# Public_CPU_Sub_Power_Supplies.net
KiCad netlist of a schematic drawn in Altium Designer
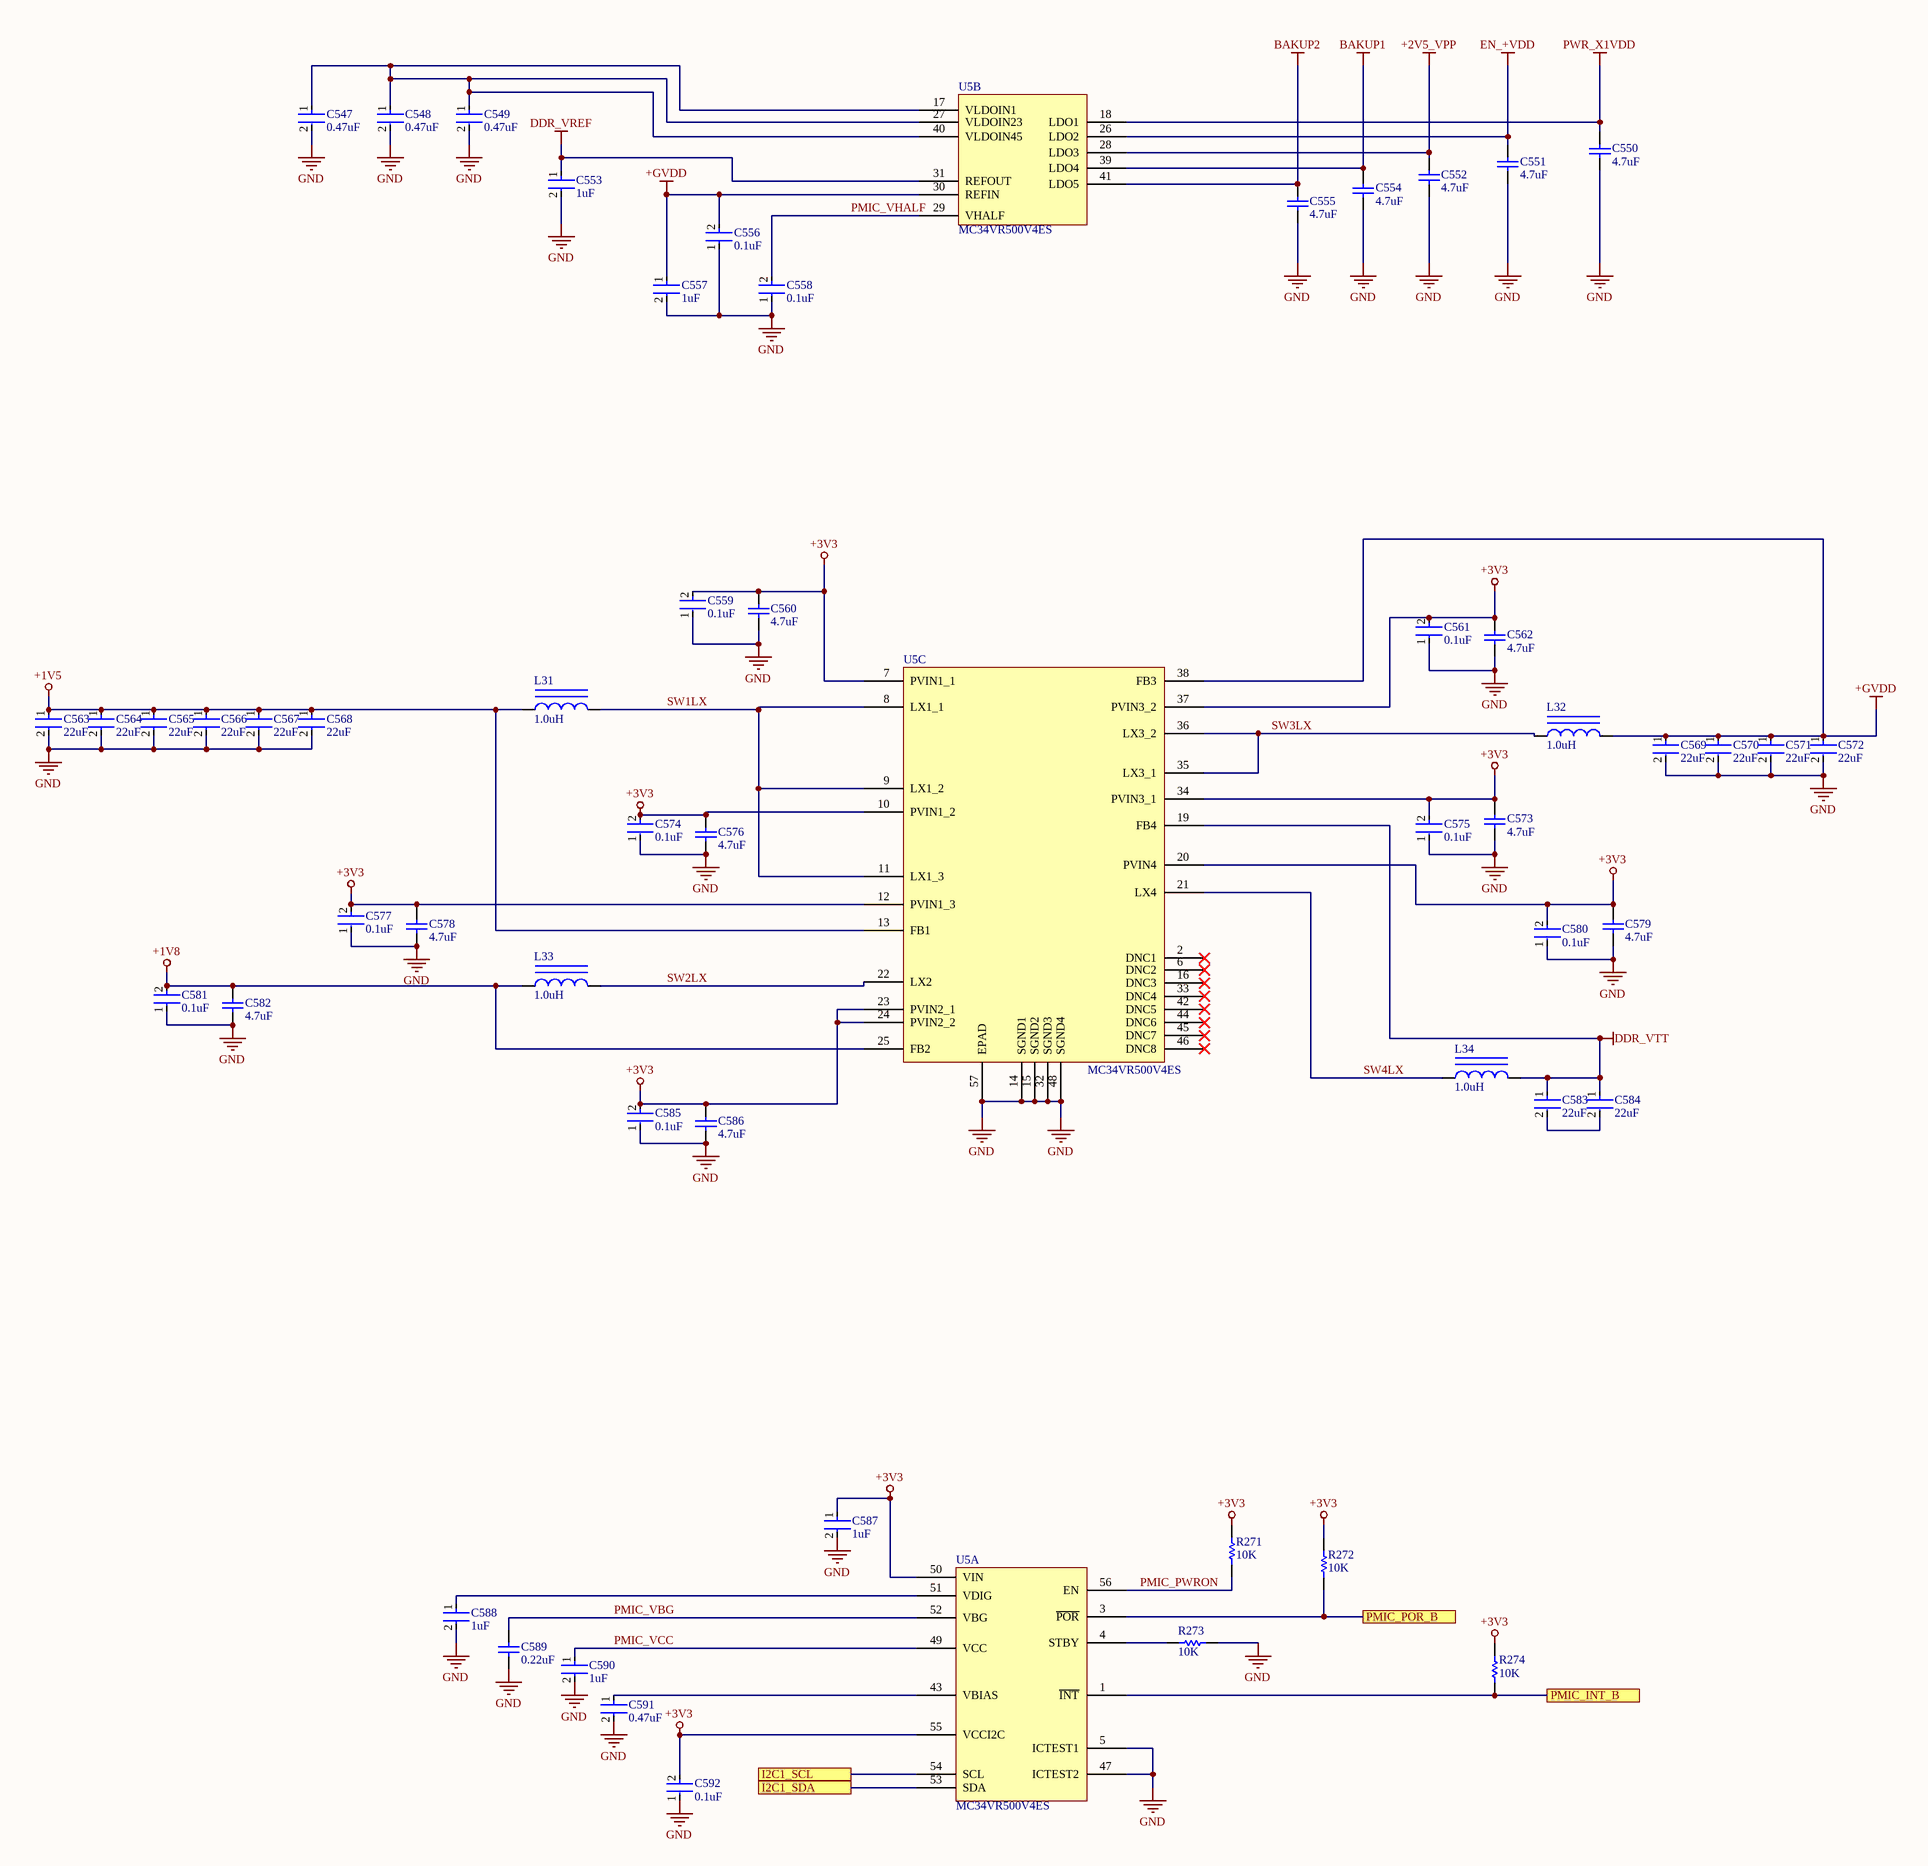
[diagram p0: Public_CPU_Sub_Power_Supplies.SchDoc]

(export (version "E")
  (design (tool "Eeschema 10.0.6"))
  (components
    (comp (ref "C547")
      (value "0.47uF")
      (footprint "FP-GRM188-0_1-e0_2_0_5-IPC_B")
      (description "Chip Multilayer Ceramic Capacitors for General Purpose, 0603, 0.47uF, X7R, 15%, 10%, 16V")
      (fields (field (name "VOLTAGE") "16V") (field (name "TOLERANCE") "10%"))
      (libsource (lib "Altium Content Vault") (part "11868f565c42a9108669ba33697ecf6"))
    )
    (comp (ref "C548")
      (value "0.47uF")
      (footprint "FP-GRM188-0_1-e0_2_0_5-IPC_B")
      (description "Chip Multilayer Ceramic Capacitors for General Purpose, 0603, 0.47uF, X7R, 15%, 10%, 16V")
      (fields (field (name "VOLTAGE") "16V") (field (name "TOLERANCE") "10%"))
      (libsource (lib "Altium Content Vault") (part "11868f565c42a9108669ba33697ecf6"))
    )
    (comp (ref "C549")
      (value "0.47uF")
      (footprint "FP-GRM188-0_1-e0_2_0_5-IPC_B")
      (description "Chip Multilayer Ceramic Capacitors for General Purpose, 0603, 0.47uF, X7R, 15%, 10%, 16V")
      (fields (field (name "VOLTAGE") "16V") (field (name "TOLERANCE") "10%"))
      (libsource (lib "Altium Content Vault") (part "11868f565c42a9108669ba33697ecf6"))
    )
    (comp (ref "C550")
      (value "4.7uF")
      (footprint "CAPC2013X145X50ML20T25")
      (fields (field (name "MANUFACTURER") "Kemet") (field (name "PART NUMBER") "C0805C475K3PACTU"))
      (libsource (lib "Altium Content Vault") (part "CAP"))
    )
    (comp (ref "C551")
      (value "4.7uF")
      (footprint "CAPC2013X145X50ML20T25")
      (fields (field (name "MANUFACTURER") "Kemet") (field (name "PART NUMBER") "C0805C475K3PACTU"))
      (libsource (lib "Altium Content Vault") (part "CAP"))
    )
    (comp (ref "C552")
      (value "4.7uF")
      (footprint "CAPC2013X145X50ML20T25")
      (fields (field (name "MANUFACTURER") "Kemet") (field (name "PART NUMBER") "C0805C475K3PACTU"))
      (libsource (lib "Altium Content Vault") (part "CAP"))
    )
    (comp (ref "C553")
      (value "1uF")
      (footprint "FP-GRM15-0_1-MFG")
      (description "CAP CER 1UF 10V X5R 0402")
      (fields
        (field (name "OCTOPART") "https://octopart.com/grm155r61a105ke15d-murata-197442")
        (field (name "MANUFACTURER PART NUMBER") "GRM155R61A105KE15D")
      )
      (libsource (lib "Altium Content Vault") (part "02cd4be3c70576c341d710602a673aa"))
    )
    (comp (ref "C554")
      (value "4.7uF")
      (footprint "CAPC2013X145X50ML20T25")
      (fields (field (name "MANUFACTURER") "Kemet") (field (name "PART NUMBER") "C0805C475K3PACTU"))
      (libsource (lib "Altium Content Vault") (part "CAP"))
    )
    (comp (ref "C555")
      (value "4.7uF")
      (footprint "CAPC2013X145X50ML20T25")
      (fields (field (name "MANUFACTURER") "Kemet") (field (name "PART NUMBER") "C0805C475K3PACTU"))
      (libsource (lib "Altium Content Vault") (part "CAP"))
    )
    (comp (ref "C556")
      (value "0.1uF")
      (footprint "FP-GRM15-MFG")
      (description "CAP CER 0.1UF 16V X7R 0402")
      (fields (field (name "MANUFACTURER PART NUMBER") "GRM155R71C104KA88D") (field (name "TOLERANCE") "10%"))
      (libsource (lib "Altium Content Vault") (part "236180d848d6139a670b325ea6854c9"))
    )
    (comp (ref "C557")
      (value "1uF")
      (footprint "FP-GRM15-0_1-MFG")
      (description "CAP CER 1UF 10V X5R 0402")
      (fields
        (field (name "OCTOPART") "https://octopart.com/grm155r61a105ke15d-murata-197442")
        (field (name "MANUFACTURER PART NUMBER") "GRM155R61A105KE15D")
      )
      (libsource (lib "Altium Content Vault") (part "02cd4be3c70576c341d710602a673aa"))
    )
    (comp (ref "C558")
      (value "0.1uF")
      (footprint "FP-GRM15-MFG")
      (description "CAP CER 0.1UF 16V X7R 0402")
      (fields (field (name "MANUFACTURER PART NUMBER") "GRM155R71C104KA88D") (field (name "TOLERANCE") "10%"))
      (libsource (lib "Altium Content Vault") (part "236180d848d6139a670b325ea6854c9"))
    )
    (comp (ref "C559")
      (value "0.1uF")
      (footprint "FP-GRM15-MFG")
      (description "CAP CER 0.1UF 16V X7R 0402")
      (fields (field (name "MANUFACTURER PART NUMBER") "GRM155R71C104KA88D") (field (name "TOLERANCE") "10%"))
      (libsource (lib "Altium Content Vault") (part "236180d848d6139a670b325ea6854c9"))
    )
    (comp (ref "C560")
      (value "4.7uF")
      (footprint "CAPC2013X145X50ML20T25")
      (fields (field (name "MANUFACTURER") "Kemet") (field (name "PART NUMBER") "C0805C475K3PACTU"))
      (libsource (lib "Altium Content Vault") (part "CAP"))
    )
    (comp (ref "C561")
      (value "0.1uF")
      (footprint "FP-GRM15-MFG")
      (description "CAP CER 0.1UF 16V X7R 0402")
      (fields (field (name "MANUFACTURER PART NUMBER") "GRM155R71C104KA88D") (field (name "TOLERANCE") "10%"))
      (libsource (lib "Altium Content Vault") (part "236180d848d6139a670b325ea6854c9"))
    )
    (comp (ref "C562")
      (value "4.7uF")
      (footprint "CAPC2013X145X50ML20T25")
      (fields (field (name "MANUFACTURER") "Kemet") (field (name "PART NUMBER") "C0805C475K3PACTU"))
      (libsource (lib "Altium Content Vault") (part "CAP"))
    )
    (comp (ref "C563")
      (value "22uF")
      (footprint "FP-GRM21B-0_15-MFG")
      (description "Chip Multilayer Ceramic Capacitors for General Purpose, 0805, 22uF, X5R, 15%, 20%, 6.3V")
      (fields (field (name "VOLTAGE") "6.3V") (field (name "TOLERANCE") "20%"))
      (libsource (lib "Altium Content Vault") (part "b4654b650e69147ec39a6b967a45e02"))
    )
    (comp (ref "C564")
      (value "22uF")
      (footprint "FP-GRM21B-0_15-MFG")
      (description "Chip Multilayer Ceramic Capacitors for General Purpose, 0805, 22uF, X5R, 15%, 20%, 6.3V")
      (fields (field (name "VOLTAGE") "6.3V") (field (name "TOLERANCE") "20%"))
      (libsource (lib "Altium Content Vault") (part "b4654b650e69147ec39a6b967a45e02"))
    )
    (comp (ref "C565")
      (value "22uF")
      (footprint "FP-GRM21B-0_15-MFG")
      (description "Chip Multilayer Ceramic Capacitors for General Purpose, 0805, 22uF, X5R, 15%, 20%, 6.3V")
      (fields (field (name "VOLTAGE") "6.3V") (field (name "TOLERANCE") "20%"))
      (libsource (lib "Altium Content Vault") (part "b4654b650e69147ec39a6b967a45e02"))
    )
    (comp (ref "C566")
      (value "22uF")
      (footprint "FP-GRM21B-0_15-MFG")
      (description "Chip Multilayer Ceramic Capacitors for General Purpose, 0805, 22uF, X5R, 15%, 20%, 6.3V")
      (fields (field (name "VOLTAGE") "6.3V") (field (name "TOLERANCE") "20%"))
      (libsource (lib "Altium Content Vault") (part "b4654b650e69147ec39a6b967a45e02"))
    )
    (comp (ref "C567")
      (value "22uF")
      (footprint "FP-GRM21B-0_15-MFG")
      (description "Chip Multilayer Ceramic Capacitors for General Purpose, 0805, 22uF, X5R, 15%, 20%, 6.3V")
      (fields (field (name "VOLTAGE") "6.3V") (field (name "TOLERANCE") "20%"))
      (libsource (lib "Altium Content Vault") (part "b4654b650e69147ec39a6b967a45e02"))
    )
    (comp (ref "C568")
      (value "22uF")
      (footprint "FP-GRM21B-0_15-MFG")
      (description "Chip Multilayer Ceramic Capacitors for General Purpose, 0805, 22uF, X5R, 15%, 20%, 6.3V")
      (fields (field (name "VOLTAGE") "6.3V") (field (name "TOLERANCE") "20%"))
      (libsource (lib "Altium Content Vault") (part "b4654b650e69147ec39a6b967a45e02"))
    )
    (comp (ref "C569")
      (value "22uF")
      (footprint "FP-GRM21B-0_15-MFG")
      (description "Chip Multilayer Ceramic Capacitors for General Purpose, 0805, 22uF, X5R, 15%, 20%, 6.3V")
      (fields (field (name "VOLTAGE") "6.3V") (field (name "TOLERANCE") "20%"))
      (libsource (lib "Altium Content Vault") (part "b4654b650e69147ec39a6b967a45e02"))
    )
    (comp (ref "C570")
      (value "22uF")
      (footprint "FP-GRM21B-0_15-MFG")
      (description "Chip Multilayer Ceramic Capacitors for General Purpose, 0805, 22uF, X5R, 15%, 20%, 6.3V")
      (fields (field (name "VOLTAGE") "6.3V") (field (name "TOLERANCE") "20%"))
      (libsource (lib "Altium Content Vault") (part "b4654b650e69147ec39a6b967a45e02"))
    )
    (comp (ref "C571")
      (value "22uF")
      (footprint "FP-GRM21B-0_15-MFG")
      (description "Chip Multilayer Ceramic Capacitors for General Purpose, 0805, 22uF, X5R, 15%, 20%, 6.3V")
      (fields (field (name "VOLTAGE") "6.3V") (field (name "TOLERANCE") "20%"))
      (libsource (lib "Altium Content Vault") (part "b4654b650e69147ec39a6b967a45e02"))
    )
    (comp (ref "C572")
      (value "22uF")
      (footprint "FP-GRM21B-0_15-MFG")
      (description "Chip Multilayer Ceramic Capacitors for General Purpose, 0805, 22uF, X5R, 15%, 20%, 6.3V")
      (fields (field (name "VOLTAGE") "6.3V") (field (name "TOLERANCE") "20%"))
      (libsource (lib "Altium Content Vault") (part "b4654b650e69147ec39a6b967a45e02"))
    )
    (comp (ref "C573")
      (value "4.7uF")
      (footprint "CAPC2013X145X50ML20T25")
      (fields (field (name "MANUFACTURER") "Kemet") (field (name "PART NUMBER") "C0805C475K3PACTU"))
      (libsource (lib "Altium Content Vault") (part "CAP"))
    )
    (comp (ref "C574")
      (value "0.1uF")
      (footprint "FP-GRM15-MFG")
      (description "CAP CER 0.1UF 16V X7R 0402")
      (fields (field (name "MANUFACTURER PART NUMBER") "GRM155R71C104KA88D") (field (name "TOLERANCE") "10%"))
      (libsource (lib "Altium Content Vault") (part "236180d848d6139a670b325ea6854c9"))
    )
    (comp (ref "C575")
      (value "0.1uF")
      (footprint "FP-GRM15-MFG")
      (description "CAP CER 0.1UF 16V X7R 0402")
      (fields (field (name "MANUFACTURER PART NUMBER") "GRM155R71C104KA88D") (field (name "TOLERANCE") "10%"))
      (libsource (lib "Altium Content Vault") (part "236180d848d6139a670b325ea6854c9"))
    )
    (comp (ref "C576")
      (value "4.7uF")
      (footprint "CAPC2013X145X50ML20T25")
      (fields (field (name "MANUFACTURER") "Kemet") (field (name "PART NUMBER") "C0805C475K3PACTU"))
      (libsource (lib "Altium Content Vault") (part "CAP"))
    )
    (comp (ref "C577")
      (value "0.1uF")
      (footprint "FP-GRM15-MFG")
      (description "CAP CER 0.1UF 16V X7R 0402")
      (fields (field (name "MANUFACTURER PART NUMBER") "GRM155R71C104KA88D") (field (name "TOLERANCE") "10%"))
      (libsource (lib "Altium Content Vault") (part "236180d848d6139a670b325ea6854c9"))
    )
    (comp (ref "C578")
      (value "4.7uF")
      (footprint "CAPC2013X145X50ML20T25")
      (fields (field (name "MANUFACTURER") "Kemet") (field (name "PART NUMBER") "C0805C475K3PACTU"))
      (libsource (lib "Altium Content Vault") (part "CAP"))
    )
    (comp (ref "C579")
      (value "4.7uF")
      (footprint "CAPC2013X145X50ML20T25")
      (fields (field (name "MANUFACTURER") "Kemet") (field (name "PART NUMBER") "C0805C475K3PACTU"))
      (libsource (lib "Altium Content Vault") (part "CAP"))
    )
    (comp (ref "C580")
      (value "0.1uF")
      (footprint "FP-GRM15-MFG")
      (description "CAP CER 0.1UF 16V X7R 0402")
      (fields (field (name "MANUFACTURER PART NUMBER") "GRM155R71C104KA88D") (field (name "TOLERANCE") "10%"))
      (libsource (lib "Altium Content Vault") (part "236180d848d6139a670b325ea6854c9"))
    )
    (comp (ref "C581")
      (value "0.1uF")
      (footprint "FP-GRM15-MFG")
      (description "CAP CER 0.1UF 16V X7R 0402")
      (fields (field (name "MANUFACTURER PART NUMBER") "GRM155R71C104KA88D") (field (name "TOLERANCE") "10%"))
      (libsource (lib "Altium Content Vault") (part "236180d848d6139a670b325ea6854c9"))
    )
    (comp (ref "C582")
      (value "4.7uF")
      (footprint "CAPC2013X145X50ML20T25")
      (fields (field (name "MANUFACTURER") "Kemet") (field (name "PART NUMBER") "C0805C475K3PACTU"))
      (libsource (lib "Altium Content Vault") (part "CAP"))
    )
    (comp (ref "C583")
      (value "22uF")
      (footprint "FP-GRM21B-0_15-MFG")
      (description "Chip Multilayer Ceramic Capacitors for General Purpose, 0805, 22uF, X5R, 15%, 20%, 6.3V")
      (fields (field (name "VOLTAGE") "6.3V") (field (name "TOLERANCE") "20%"))
      (libsource (lib "Altium Content Vault") (part "b4654b650e69147ec39a6b967a45e02"))
    )
    (comp (ref "C584")
      (value "22uF")
      (footprint "FP-GRM21B-0_15-MFG")
      (description "Chip Multilayer Ceramic Capacitors for General Purpose, 0805, 22uF, X5R, 15%, 20%, 6.3V")
      (fields (field (name "VOLTAGE") "6.3V") (field (name "TOLERANCE") "20%"))
      (libsource (lib "Altium Content Vault") (part "b4654b650e69147ec39a6b967a45e02"))
    )
    (comp (ref "C585")
      (value "0.1uF")
      (footprint "FP-GRM15-MFG")
      (description "CAP CER 0.1UF 16V X7R 0402")
      (fields (field (name "MANUFACTURER PART NUMBER") "GRM155R71C104KA88D") (field (name "TOLERANCE") "10%"))
      (libsource (lib "Altium Content Vault") (part "236180d848d6139a670b325ea6854c9"))
    )
    (comp (ref "C586")
      (value "4.7uF")
      (footprint "CAPC2013X145X50ML20T25")
      (fields (field (name "MANUFACTURER") "Kemet") (field (name "PART NUMBER") "C0805C475K3PACTU"))
      (libsource (lib "Altium Content Vault") (part "CAP"))
    )
    (comp (ref "C587")
      (value "1uF")
      (footprint "FP-GRM15-0_1-MFG")
      (description "CAP CER 1UF 10V X5R 0402")
      (fields
        (field (name "OCTOPART") "https://octopart.com/grm155r61a105ke15d-murata-197442")
        (field (name "MANUFACTURER PART NUMBER") "GRM155R61A105KE15D")
      )
      (libsource (lib "Altium Content Vault") (part "02cd4be3c70576c341d710602a673aa"))
    )
    (comp (ref "C588")
      (value "1uF")
      (footprint "FP-GRM15-0_1-MFG")
      (description "CAP CER 1UF 10V X5R 0402")
      (fields
        (field (name "OCTOPART") "https://octopart.com/grm155r61a105ke15d-murata-197442")
        (field (name "MANUFACTURER PART NUMBER") "GRM155R61A105KE15D")
      )
      (libsource (lib "Altium Content Vault") (part "02cd4be3c70576c341d710602a673aa"))
    )
    (comp (ref "C589")
      (value "0.22uF")
      (footprint "CAPC1005X55X25NL05T10")
      (description "Chip Capacitor, 220 nF, +/- 10%, 10 V, -55 to 85 degC, 0402 (1005 Metric), RoHS, Tape and Reel")
      (fields (field (name "MANUFACTURER") "Basic Passives") (field (name "TOLERANCE") "10%"))
      (libsource (lib "Altium Content Vault") (part "CAP-NP-2"))
    )
    (comp (ref "C590")
      (value "1uF")
      (footprint "FP-GRM15-0_1-MFG")
      (description "CAP CER 1UF 10V X5R 0402")
      (fields
        (field (name "OCTOPART") "https://octopart.com/grm155r61a105ke15d-murata-197442")
        (field (name "MANUFACTURER PART NUMBER") "GRM155R61A105KE15D")
      )
      (libsource (lib "Altium Content Vault") (part "02cd4be3c70576c341d710602a673aa"))
    )
    (comp (ref "C591")
      (value "0.47uF")
      (footprint "FP-GRM188-0_1-e0_2_0_5-IPC_B")
      (description "Chip Multilayer Ceramic Capacitors for General Purpose, 0603, 0.47uF, X7R, 15%, 10%, 16V")
      (fields (field (name "VOLTAGE") "16V") (field (name "TOLERANCE") "10%"))
      (libsource (lib "Altium Content Vault") (part "11868f565c42a9108669ba33697ecf6"))
    )
    (comp (ref "C592")
      (value "0.1uF")
      (footprint "FP-GRM15-MFG")
      (description "CAP CER 0.1UF 16V X7R 0402")
      (fields (field (name "MANUFACTURER PART NUMBER") "GRM155R71C104KA88D") (field (name "TOLERANCE") "10%"))
      (libsource (lib "Altium Content Vault") (part "236180d848d6139a670b325ea6854c9"))
    )
    (comp (ref "L31")
      (value "1.0uH")
      (footprint "BOUR-CM45_L")
      (description "Chip Inductor, 1 uH, +/- 10%, 450 mA, -40 to 125 degC, 2-Pin SMD (1812), RoHS, Tape and Reel")
      (fields (field (name "MANUFACTURER") "Bourns"))
      (libsource (lib "Altium Content Vault") (part "IND-IRON-2"))
    )
    (comp (ref "L32")
      (value "1.0uH")
      (footprint "BOUR-CM45_L")
      (description "Chip Inductor, 1 uH, +/- 10%, 450 mA, -40 to 125 degC, 2-Pin SMD (1812), RoHS, Tape and Reel")
      (fields (field (name "MANUFACTURER") "Bourns"))
      (libsource (lib "Altium Content Vault") (part "IND-IRON-2"))
    )
    (comp (ref "L33")
      (value "1.0uH")
      (footprint "BOUR-CM45_L")
      (description "Chip Inductor, 1 uH, +/- 10%, 450 mA, -40 to 125 degC, 2-Pin SMD (1812), RoHS, Tape and Reel")
      (fields (field (name "MANUFACTURER") "Bourns"))
      (libsource (lib "Altium Content Vault") (part "IND-IRON-2"))
    )
    (comp (ref "L34")
      (value "1.0uH")
      (footprint "BOUR-CM45_L")
      (description "Chip Inductor, 1 uH, +/- 10%, 450 mA, -40 to 125 degC, 2-Pin SMD (1812), RoHS, Tape and Reel")
      (fields (field (name "MANUFACTURER") "Bourns"))
      (libsource (lib "Altium Content Vault") (part "IND-IRON-2"))
    )
    (comp (ref "R271")
      (value "10K")
      (footprint "RESC1005X40X25LL05T05")
      (description "Chip Resistor, 10 KOhm, +/- 1%, 0.1 W, -55 to 155 degC, 0402 (1005 Metric), RoHS, Tape and Reel")
      (fields (field (name "TOLERANCE") "1%") (field (name "MANUFACTURER") "Panasonic"))
      (libsource (lib "Altium Content Vault") (part "RES-2"))
    )
    (comp (ref "R272")
      (value "10K")
      (footprint "RESC1005X40X25LL05T05")
      (description "Chip Resistor, 10 KOhm, +/- 1%, 0.1 W, -55 to 155 degC, 0402 (1005 Metric), RoHS, Tape and Reel")
      (fields (field (name "TOLERANCE") "1%") (field (name "MANUFACTURER") "Panasonic"))
      (libsource (lib "Altium Content Vault") (part "RES-2"))
    )
    (comp (ref "R273")
      (value "10K")
      (footprint "RESC1005X40X25LL05T05")
      (description "Chip Resistor, 10 KOhm, +/- 1%, 0.1 W, -55 to 155 degC, 0402 (1005 Metric), RoHS, Tape and Reel")
      (fields (field (name "TOLERANCE") "1%") (field (name "MANUFACTURER") "Panasonic"))
      (libsource (lib "Altium Content Vault") (part "RES-2"))
    )
    (comp (ref "R274")
      (value "10K")
      (footprint "RESC1005X40X25LL05T05")
      (description "Chip Resistor, 10 KOhm, +/- 1%, 0.1 W, -55 to 155 degC, 0402 (1005 Metric), RoHS, Tape and Reel")
      (fields (field (name "TOLERANCE") "1%") (field (name "MANUFACTURER") "Panasonic"))
      (libsource (lib "Altium Content Vault") (part "RES-2"))
    )
    (comp (ref "U5")
      (value "MC34VR500V4ES")
      (footprint "MC34VR500V4ES:QFN50P800X800X90-57N")
      (description "Regulator, Buck, Quad with up to 4.5A Output and Triple User-programmable LDOs, QFN 56, Tray")
      (fields (field (name "MF") "{'manufacturer': u'NXP Semiconductors'}"))
      (libsource (lib "MC34VR500V4ES") (part "MC34VR500V4ES"))
    )
  )
  (nets
    (net (code "1") (name "+1V5") (class "Default")
      (node (ref "C563") (pin "1") (pinfunction "1_1") (pintype "passive"))
      (node (ref "C564") (pin "1") (pinfunction "1_1") (pintype "passive"))
      (node (ref "C565") (pin "1") (pinfunction "1_1") (pintype "passive"))
      (node (ref "C566") (pin "1") (pinfunction "1_1") (pintype "passive"))
      (node (ref "C567") (pin "1") (pinfunction "1_1") (pintype "passive"))
      (node (ref "C568") (pin "1") (pinfunction "1_1") (pintype "passive"))
      (node (ref "L31") (pin "1") (pinfunction "1_1") (pintype "passive"))
      (node (ref "U5") (pin "13") (pinfunction "FB1_13") (pintype "passive"))
    )
    (net (code "2") (name "+1V8") (class "Default")
      (node (ref "C581") (pin "2") (pinfunction "2_2") (pintype "passive"))
      (node (ref "C582") (pin "2") (pinfunction "2_2") (pintype "passive"))
      (node (ref "L33") (pin "1") (pinfunction "1_1") (pintype "passive"))
      (node (ref "U5") (pin "25") (pinfunction "FB2_25") (pintype "passive"))
    )
    (net (code "3") (name "+2V5_VPP") (class "Default")
      (node (ref "C552") (pin "2") (pinfunction "2_2") (pintype "passive"))
      (node (ref "U5") (pin "28") (pinfunction "LDO3_28") (pintype "passive"))
    )
    (net (code "4") (name "+3V3") (class "Default")
      (node (ref "C559") (pin "2") (pinfunction "2_2") (pintype "passive"))
      (node (ref "C560") (pin "2") (pinfunction "2_2") (pintype "passive"))
      (node (ref "C561") (pin "2") (pinfunction "2_2") (pintype "passive"))
      (node (ref "C562") (pin "2") (pinfunction "2_2") (pintype "passive"))
      (node (ref "C573") (pin "2") (pinfunction "2_2") (pintype "passive"))
      (node (ref "C574") (pin "2") (pinfunction "2_2") (pintype "passive"))
      (node (ref "C575") (pin "2") (pinfunction "2_2") (pintype "passive"))
      (node (ref "C576") (pin "2") (pinfunction "2_2") (pintype "passive"))
      (node (ref "C577") (pin "2") (pinfunction "2_2") (pintype "passive"))
      (node (ref "C578") (pin "2") (pinfunction "2_2") (pintype "passive"))
      (node (ref "C579") (pin "2") (pinfunction "2_2") (pintype "passive"))
      (node (ref "C580") (pin "2") (pinfunction "2_2") (pintype "passive"))
      (node (ref "C585") (pin "2") (pinfunction "2_2") (pintype "passive"))
      (node (ref "C586") (pin "2") (pinfunction "2_2") (pintype "passive"))
      (node (ref "C587") (pin "1") (pinfunction "1_1") (pintype "passive"))
      (node (ref "C592") (pin "2") (pinfunction "2_2") (pintype "passive"))
      (node (ref "R271") (pin "2") (pinfunction "2_2") (pintype "passive"))
      (node (ref "R272") (pin "2") (pinfunction "2_2") (pintype "passive"))
      (node (ref "R274") (pin "2") (pinfunction "2_2") (pintype "passive"))
      (node (ref "U5") (pin "10") (pinfunction "PVIN1_2_10") (pintype "passive"))
      (node (ref "U5") (pin "12") (pinfunction "PVIN1_3_12") (pintype "passive"))
      (node (ref "U5") (pin "20") (pinfunction "PVIN4_20") (pintype "passive"))
      (node (ref "U5") (pin "23") (pinfunction "PVIN2_1_23") (pintype "passive"))
      (node (ref "U5") (pin "24") (pinfunction "PVIN2_2_24") (pintype "passive"))
      (node (ref "U5") (pin "34") (pinfunction "PVIN3_1_34") (pintype "passive"))
      (node (ref "U5") (pin "37") (pinfunction "PVIN3_2_37") (pintype "passive"))
      (node (ref "U5") (pin "50") (pinfunction "VIN_50") (pintype "passive"))
      (node (ref "U5") (pin "55") (pinfunction "VCCI2C_55") (pintype "passive"))
      (node (ref "U5") (pin "7") (pinfunction "PVIN1_1_7") (pintype "passive"))
    )
    (net (code "5") (name "+GVDD") (class "Default")
      (node (ref "C556") (pin "2") (pinfunction "2_2") (pintype "passive"))
      (node (ref "C557") (pin "1") (pinfunction "1_1") (pintype "passive"))
      (node (ref "C569") (pin "1") (pinfunction "1_1") (pintype "passive"))
      (node (ref "C570") (pin "1") (pinfunction "1_1") (pintype "passive"))
      (node (ref "C571") (pin "1") (pinfunction "1_1") (pintype "passive"))
      (node (ref "C572") (pin "1") (pinfunction "1_1") (pintype "passive"))
      (node (ref "L32") (pin "2") (pinfunction "2_2") (pintype "passive"))
      (node (ref "U5") (pin "30") (pinfunction "REFIN_30") (pintype "passive"))
      (node (ref "U5") (pin "38") (pinfunction "FB3_38") (pintype "passive"))
    )
    (net (code "6") (name "/I2C1_SCL") (class "Default")
      (node (ref "U5") (pin "54") (pinfunction "SCL_54") (pintype "passive"))
    )
    (net (code "7") (name "/I2C1_SDA") (class "Default")
      (node (ref "U5") (pin "53") (pinfunction "SDA_53") (pintype "passive"))
    )
    (net (code "8") (name "/PMIC_INT_B") (class "Default")
      (node (ref "R274") (pin "1") (pinfunction "1_1") (pintype "passive"))
      (node (ref "U5") (pin "1") (pinfunction "~{INT}_1") (pintype "passive"))
    )
    (net (code "9") (name "/PMIC_POR_B") (class "Default")
      (node (ref "R272") (pin "1") (pinfunction "1_1") (pintype "passive"))
      (node (ref "U5") (pin "3") (pinfunction "~{POR}_3") (pintype "passive"))
    )
    (net (code "10") (name "/PMIC_PWRON") (class "Default")
      (node (ref "R271") (pin "1") (pinfunction "1_1") (pintype "passive"))
      (node (ref "U5") (pin "56") (pinfunction "EN_56") (pintype "passive"))
    )
    (net (code "11") (name "/PMIC_VBG") (class "Default")
      (node (ref "C589") (pin "2") (pinfunction "2_2") (pintype "passive"))
      (node (ref "U5") (pin "52") (pinfunction "VBG_52") (pintype "passive"))
    )
    (net (code "12") (name "/PMIC_VCC") (class "Default")
      (node (ref "C590") (pin "1") (pinfunction "1_1") (pintype "passive"))
      (node (ref "U5") (pin "49") (pinfunction "VCC_49") (pintype "passive"))
    )
    (net (code "13") (name "/PMIC_VHALF") (class "Default")
      (node (ref "C558") (pin "2") (pinfunction "2_2") (pintype "passive"))
      (node (ref "U5") (pin "29") (pinfunction "VHALF_29") (pintype "passive"))
    )
    (net (code "14") (name "/SW1LX") (class "Default")
      (node (ref "L31") (pin "2") (pinfunction "2_2") (pintype "passive"))
      (node (ref "U5") (pin "11") (pinfunction "LX1_3_11") (pintype "passive"))
      (node (ref "U5") (pin "8") (pinfunction "LX1_1_8") (pintype "passive"))
      (node (ref "U5") (pin "9") (pinfunction "LX1_2_9") (pintype "passive"))
    )
    (net (code "15") (name "/SW2LX") (class "Default")
      (node (ref "L33") (pin "2") (pinfunction "2_2") (pintype "passive"))
      (node (ref "U5") (pin "22") (pinfunction "LX2_22") (pintype "passive"))
    )
    (net (code "16") (name "/SW3LX") (class "Default")
      (node (ref "L32") (pin "1") (pinfunction "1_1") (pintype "passive"))
      (node (ref "U5") (pin "35") (pinfunction "LX3_1_35") (pintype "passive"))
      (node (ref "U5") (pin "36") (pinfunction "LX3_2_36") (pintype "passive"))
    )
    (net (code "17") (name "/SW4LX") (class "Default")
      (node (ref "L34") (pin "1") (pinfunction "1_1") (pintype "passive"))
      (node (ref "U5") (pin "21") (pinfunction "LX4_21") (pintype "passive"))
    )
    (net (code "18") (name "BAKUP1") (class "Default")
      (node (ref "C554") (pin "2") (pinfunction "2_2") (pintype "passive"))
      (node (ref "U5") (pin "39") (pinfunction "LDO4_39") (pintype "passive"))
    )
    (net (code "19") (name "BAKUP2") (class "Default")
      (node (ref "C555") (pin "2") (pinfunction "2_2") (pintype "passive"))
      (node (ref "U5") (pin "41") (pinfunction "LDO5_41") (pintype "passive"))
    )
    (net (code "20") (name "DDR_VREF") (class "Default")
      (node (ref "C553") (pin "1") (pinfunction "1_1") (pintype "passive"))
      (node (ref "U5") (pin "31") (pinfunction "REFOUT_31") (pintype "passive"))
    )
    (net (code "21") (name "DDR_VTT") (class "Default")
      (node (ref "C583") (pin "1") (pinfunction "1_1") (pintype "passive"))
      (node (ref "C584") (pin "1") (pinfunction "1_1") (pintype "passive"))
      (node (ref "L34") (pin "2") (pinfunction "2_2") (pintype "passive"))
      (node (ref "U5") (pin "19") (pinfunction "FB4_19") (pintype "passive"))
    )
    (net (code "22") (name "EN_+VDD") (class "Default")
      (node (ref "C551") (pin "2") (pinfunction "2_2") (pintype "passive"))
      (node (ref "U5") (pin "26") (pinfunction "LDO2_26") (pintype "passive"))
    )
    (net (code "23") (name "GND") (class "Default")
      (node (ref "C547") (pin "2") (pinfunction "2_2") (pintype "passive"))
      (node (ref "C548") (pin "2") (pinfunction "2_2") (pintype "passive"))
      (node (ref "C549") (pin "2") (pinfunction "2_2") (pintype "passive"))
      (node (ref "C550") (pin "1") (pinfunction "1_1") (pintype "passive"))
      (node (ref "C551") (pin "1") (pinfunction "1_1") (pintype "passive"))
      (node (ref "C552") (pin "1") (pinfunction "1_1") (pintype "passive"))
      (node (ref "C553") (pin "2") (pinfunction "2_2") (pintype "passive"))
      (node (ref "C554") (pin "1") (pinfunction "1_1") (pintype "passive"))
      (node (ref "C555") (pin "1") (pinfunction "1_1") (pintype "passive"))
      (node (ref "C556") (pin "1") (pinfunction "1_1") (pintype "passive"))
      (node (ref "C557") (pin "2") (pinfunction "2_2") (pintype "passive"))
      (node (ref "C558") (pin "1") (pinfunction "1_1") (pintype "passive"))
      (node (ref "C559") (pin "1") (pinfunction "1_1") (pintype "passive"))
      (node (ref "C560") (pin "1") (pinfunction "1_1") (pintype "passive"))
      (node (ref "C561") (pin "1") (pinfunction "1_1") (pintype "passive"))
      (node (ref "C562") (pin "1") (pinfunction "1_1") (pintype "passive"))
      (node (ref "C563") (pin "2") (pinfunction "2_2") (pintype "passive"))
      (node (ref "C564") (pin "2") (pinfunction "2_2") (pintype "passive"))
      (node (ref "C565") (pin "2") (pinfunction "2_2") (pintype "passive"))
      (node (ref "C566") (pin "2") (pinfunction "2_2") (pintype "passive"))
      (node (ref "C567") (pin "2") (pinfunction "2_2") (pintype "passive"))
      (node (ref "C568") (pin "2") (pinfunction "2_2") (pintype "passive"))
      (node (ref "C569") (pin "2") (pinfunction "2_2") (pintype "passive"))
      (node (ref "C570") (pin "2") (pinfunction "2_2") (pintype "passive"))
      (node (ref "C571") (pin "2") (pinfunction "2_2") (pintype "passive"))
      (node (ref "C572") (pin "2") (pinfunction "2_2") (pintype "passive"))
      (node (ref "C573") (pin "1") (pinfunction "1_1") (pintype "passive"))
      (node (ref "C574") (pin "1") (pinfunction "1_1") (pintype "passive"))
      (node (ref "C575") (pin "1") (pinfunction "1_1") (pintype "passive"))
      (node (ref "C576") (pin "1") (pinfunction "1_1") (pintype "passive"))
      (node (ref "C577") (pin "1") (pinfunction "1_1") (pintype "passive"))
      (node (ref "C578") (pin "1") (pinfunction "1_1") (pintype "passive"))
      (node (ref "C579") (pin "1") (pinfunction "1_1") (pintype "passive"))
      (node (ref "C580") (pin "1") (pinfunction "1_1") (pintype "passive"))
      (node (ref "C581") (pin "1") (pinfunction "1_1") (pintype "passive"))
      (node (ref "C582") (pin "1") (pinfunction "1_1") (pintype "passive"))
      (node (ref "C585") (pin "1") (pinfunction "1_1") (pintype "passive"))
      (node (ref "C586") (pin "1") (pinfunction "1_1") (pintype "passive"))
      (node (ref "C587") (pin "2") (pinfunction "2_2") (pintype "passive"))
      (node (ref "C588") (pin "2") (pinfunction "2_2") (pintype "passive"))
      (node (ref "C589") (pin "1") (pinfunction "1_1") (pintype "passive"))
      (node (ref "C590") (pin "2") (pinfunction "2_2") (pintype "passive"))
      (node (ref "C591") (pin "2") (pinfunction "2_2") (pintype "passive"))
      (node (ref "C592") (pin "1") (pinfunction "1_1") (pintype "passive"))
      (node (ref "R273") (pin "1") (pinfunction "1_1") (pintype "passive"))
      (node (ref "U5") (pin "14") (pinfunction "SGND1_14") (pintype "passive"))
      (node (ref "U5") (pin "15") (pinfunction "SGND2_15") (pintype "passive"))
      (node (ref "U5") (pin "32") (pinfunction "SGND3_32") (pintype "passive"))
      (node (ref "U5") (pin "47") (pinfunction "ICTEST2_47") (pintype "passive"))
      (node (ref "U5") (pin "48") (pinfunction "SGND4_48") (pintype "passive"))
      (node (ref "U5") (pin "5") (pinfunction "ICTEST1_5") (pintype "passive"))
      (node (ref "U5") (pin "57") (pinfunction "EPAD_57") (pintype "passive"))
    )
    (net (code "24") (name "Net-(C583-Pad2)") (class "Default")
      (node (ref "C583") (pin "2") (pinfunction "2_2") (pintype "passive"))
      (node (ref "C584") (pin "2") (pinfunction "2_2") (pintype "passive"))
    )
    (net (code "25") (name "Net-(U5A-STBY)") (class "Default")
      (node (ref "R273") (pin "2") (pinfunction "2_2") (pintype "passive"))
      (node (ref "U5") (pin "4") (pinfunction "STBY_4") (pintype "passive"))
    )
    (net (code "26") (name "Net-(U5A-VBIAS)") (class "Default")
      (node (ref "C591") (pin "1") (pinfunction "1_1") (pintype "passive"))
      (node (ref "U5") (pin "43") (pinfunction "VBIAS_43") (pintype "passive"))
    )
    (net (code "27") (name "Net-(U5A-VDIG)") (class "Default")
      (node (ref "C588") (pin "1") (pinfunction "1_1") (pintype "passive"))
      (node (ref "U5") (pin "51") (pinfunction "VDIG_51") (pintype "passive"))
    )
    (net (code "28") (name "Net-(U5B-VLDOIN1)") (class "Default")
      (node (ref "C547") (pin "1") (pinfunction "1_1") (pintype "passive"))
      (node (ref "C548") (pin "1") (pinfunction "1_1") (pintype "passive"))
      (node (ref "C549") (pin "1") (pinfunction "1_1") (pintype "passive"))
      (node (ref "U5") (pin "17") (pinfunction "VLDOIN1_17") (pintype "passive"))
      (node (ref "U5") (pin "27") (pinfunction "VLDOIN23_27") (pintype "passive"))
      (node (ref "U5") (pin "40") (pinfunction "VLDOIN45_40") (pintype "passive"))
    )
    (net (code "29") (name "PWR_X1VDD") (class "Default")
      (node (ref "C550") (pin "2") (pinfunction "2_2") (pintype "passive"))
      (node (ref "U5") (pin "18") (pinfunction "LDO1_18") (pintype "passive"))
    )
    (net (code "30") (name "unconnected-(U5C-DNC1-Pad2)") (class "Default")
      (node (ref "U5") (pin "2") (pinfunction "DNC1_2") (pintype "passive+no_connect"))
    )
    (net (code "31") (name "unconnected-(U5C-DNC2-Pad6)") (class "Default")
      (node (ref "U5") (pin "6") (pinfunction "DNC2_6") (pintype "passive+no_connect"))
    )
    (net (code "32") (name "unconnected-(U5C-DNC3-Pad16)") (class "Default")
      (node (ref "U5") (pin "16") (pinfunction "DNC3_16") (pintype "passive+no_connect"))
    )
    (net (code "33") (name "unconnected-(U5C-DNC4-Pad33)") (class "Default")
      (node (ref "U5") (pin "33") (pinfunction "DNC4_33") (pintype "passive+no_connect"))
    )
    (net (code "34") (name "unconnected-(U5C-DNC5-Pad42)") (class "Default")
      (node (ref "U5") (pin "42") (pinfunction "DNC5_42") (pintype "passive+no_connect"))
    )
    (net (code "35") (name "unconnected-(U5C-DNC6-Pad44)") (class "Default")
      (node (ref "U5") (pin "44") (pinfunction "DNC6_44") (pintype "passive+no_connect"))
    )
    (net (code "36") (name "unconnected-(U5C-DNC7-Pad45)") (class "Default")
      (node (ref "U5") (pin "45") (pinfunction "DNC7_45") (pintype "passive+no_connect"))
    )
    (net (code "37") (name "unconnected-(U5C-DNC8-Pad46)") (class "Default")
      (node (ref "U5") (pin "46") (pinfunction "DNC8_46") (pintype "passive+no_connect"))
    )
  )
)
